# Shield.net
KiCad netlist of a schematic drawn in EAGLE
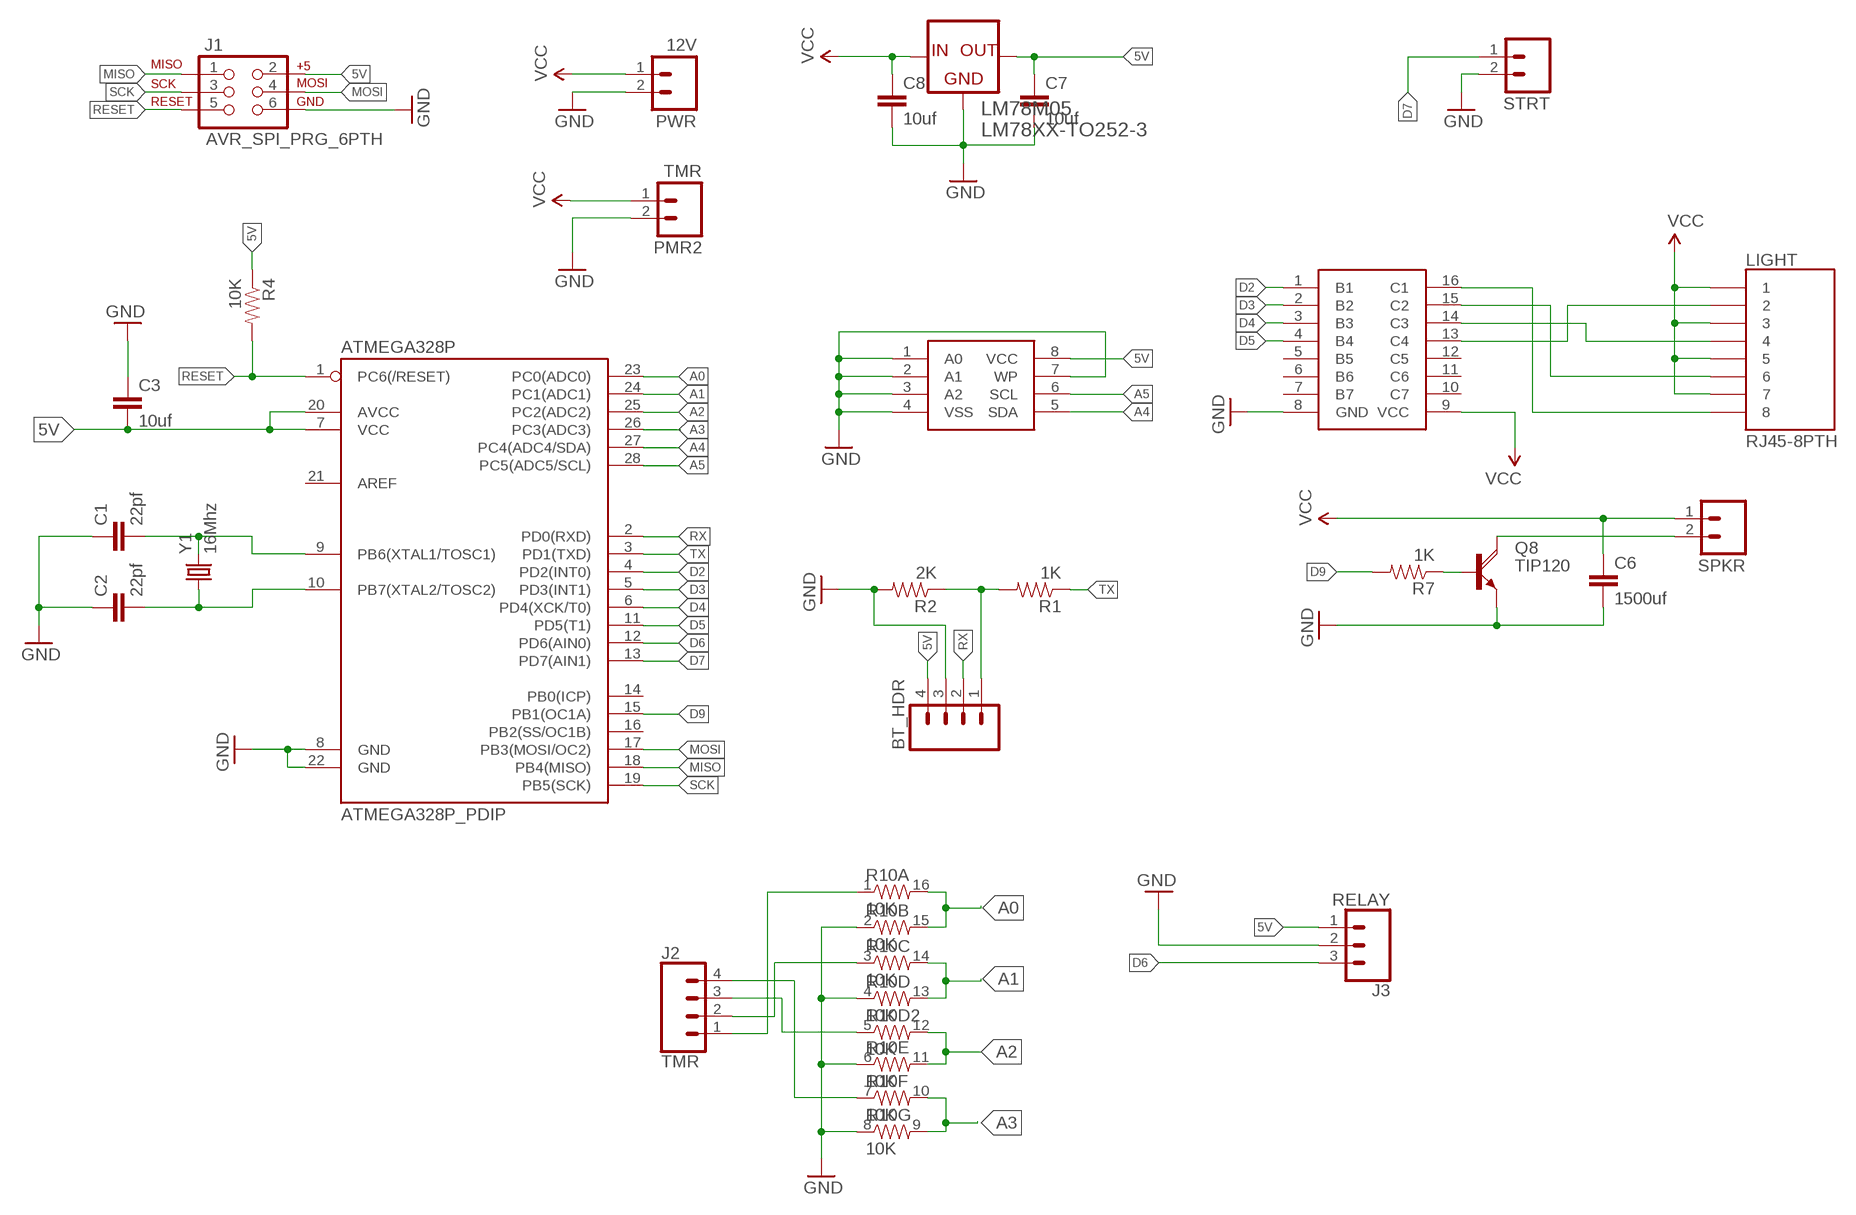
[diagram p0: schematic, sheet 1]

(export (version "E")
  (design (tool "Eeschema 10.0.6"))
  (components
    (comp (ref "24AA512")
      (value "24AAXXX")
      (footprint "eagle-import:SOIC-8-EIAJ")
      (libsource (lib "eagle-import") (part "24AAXXX"))
    )
    (comp (ref "ATMEGA328P")
      (value "ATMEGA328P_PDIP")
      (footprint "eagle-import:DIL28-3")
      (libsource (lib "eagle-import") (part "ATMEGA328P_PDIP"))
    )
    (comp (ref "BT_HDR")
      (value "M04PTH")
      (footprint "eagle-import:1X04@1")
      (libsource (lib "eagle-import") (part "M04PTH"))
    )
    (comp (ref "C1")
      (value "22pf")
      (footprint "eagle-import:1206")
      (libsource (lib "eagle-import") (part "CAP1206"))
    )
    (comp (ref "C2")
      (value "22pf")
      (footprint "eagle-import:1206")
      (libsource (lib "eagle-import") (part "CAP1206"))
    )
    (comp (ref "C3")
      (value "10uf")
      (footprint "eagle-import:1206")
      (libsource (lib "eagle-import") (part "CAP1206"))
    )
    (comp (ref "C6")
      (value "1500uf")
      (footprint "eagle-import:CAP-PTH-5MM")
      (libsource (lib "eagle-import") (part "CAPPTH1"))
    )
    (comp (ref "C7")
      (value "10uf")
      (footprint "eagle-import:CAP-PTH-SMALL")
      (libsource (lib "eagle-import") (part "CAPPTH"))
    )
    (comp (ref "C8")
      (value "10uf")
      (footprint "eagle-import:CAP-PTH-SMALL")
      (libsource (lib "eagle-import") (part "CAPPTH"))
    )
    (comp (ref "J1")
      (value "AVR_SPI_PRG_6PTH")
      (footprint "eagle-import:2X3")
      (libsource (lib "eagle-import") (part "AVR_SPI_PRG_6PTH"))
    )
    (comp (ref "J2")
      (value "TMR")
      (footprint "eagle-import:SCREWTERMINAL-3.5MM-4")
      (libsource (lib "eagle-import") (part "CONN_04SCREW"))
    )
    (comp (ref "J3")
      (value "RELAY")
      (footprint "eagle-import:SCREWTERMINAL-3.5MM-3")
      (libsource (lib "eagle-import") (part "CONN_03SCREW"))
    )
    (comp (ref "LIGHT")
      (value "RJ45-8PTH")
      (footprint "eagle-import:RJ45-8")
      (libsource (lib "eagle-import") (part "RJ45-8PTH"))
    )
    (comp (ref "LM78M05")
      (value "LM78XX-TO252-3")
      (footprint "eagle-import:TO252-3")
      (fields (field (name "MPN") "UA78M33CKVURG3"))
      (libsource (lib "eagle-import") (part "LM78XX-TO252-3"))
    )
    (comp (ref "MC1413D")
      (value "MC1413D")
      (footprint "eagle-import:SO016")
      (libsource (lib "eagle-import") (part "MC1413D"))
    )
    (comp (ref "PMR2")
      (value "TMR")
      (footprint "eagle-import:SCREWTERMINAL-3.5MM-2")
      (libsource (lib "eagle-import") (part "M023.5MM"))
    )
    (comp (ref "PWR")
      (value "12V")
      (footprint "eagle-import:SCREWTERMINAL-3.5MM-2")
      (libsource (lib "eagle-import") (part "M023.5MM"))
    )
    (comp (ref "Q8")
      (value "TIP120")
      (footprint "eagle-import:TO220V")
      (libsource (lib "eagle-import") (part "TIP120"))
    )
    (comp (ref "R1")
      (value "1K")
      (footprint "eagle-import:1206")
      (libsource (lib "eagle-import") (part "RESISTOR1206"))
    )
    (comp (ref "R2")
      (value "2K")
      (footprint "eagle-import:1206")
      (libsource (lib "eagle-import") (part "RESISTOR1206"))
    )
    (comp (ref "R4")
      (value "10K")
      (footprint "eagle-import:1206")
      (libsource (lib "eagle-import") (part "RESISTOR1206"))
    )
    (comp (ref "R7")
      (value "1K")
      (footprint "eagle-import:1206")
      (libsource (lib "eagle-import") (part "RESISTOR1206"))
    )
    (comp (ref "R10")
      (value "10K")
      (footprint "eagle-import:SO016")
      (libsource (lib "eagle-import") (part "RESISTOR-ARRAY"))
    )
    (comp (ref "SPKR")
      (value "M023.5MM")
      (footprint "eagle-import:SCREWTERMINAL-3.5MM-2")
      (libsource (lib "eagle-import") (part "M023.5MM"))
    )
    (comp (ref "STRT")
      (value "M023.5MM")
      (footprint "eagle-import:SCREWTERMINAL-3.5MM-2")
      (libsource (lib "eagle-import") (part "M023.5MM"))
    )
    (comp (ref "Y1")
      (value "16Mhz")
      (footprint "eagle-import:HC49US")
      (libsource (lib "eagle-import") (part "CRYSTALHC49US"))
    )
  )
  (nets
    (net (code "1") (name "5V") (class "Default")
      (node (ref "24AA512") (pin "8") (pinfunction "VCC_8") (pintype "bidirectional"))
      (node (ref "ATMEGA328P") (pin "20") (pinfunction "AVCC_20") (pintype "bidirectional"))
      (node (ref "ATMEGA328P") (pin "7") (pinfunction "VCC_7") (pintype "bidirectional"))
      (node (ref "BT_HDR") (pin "4") (pinfunction "4_4") (pintype "passive"))
      (node (ref "C3") (pin "2") (pinfunction "2_2") (pintype "passive"))
      (node (ref "C7") (pin "1") (pinfunction "1_1") (pintype "passive"))
      (node (ref "J1") (pin "2") (pinfunction "2_2") (pintype "passive"))
      (node (ref "J3") (pin "1") (pinfunction "1_1") (pintype "passive"))
      (node (ref "LM78M05") (pin "3") (pinfunction "OUT_3") (pintype "output"))
      (node (ref "R4") (pin "1") (pinfunction "1_1") (pintype "passive"))
    )
    (net (code "2") (name "A0") (class "Default")
      (node (ref "ATMEGA328P") (pin "23") (pinfunction "PC0(ADC0)_23") (pintype "bidirectional"))
      (node (ref "R10") (pin "15") (pinfunction "2_15") (pintype "passive"))
      (node (ref "R10") (pin "16") (pinfunction "2_16") (pintype "passive"))
    )
    (net (code "3") (name "A1") (class "Default")
      (node (ref "ATMEGA328P") (pin "24") (pinfunction "PC1(ADC1)_24") (pintype "bidirectional"))
      (node (ref "R10") (pin "13") (pinfunction "2_13") (pintype "passive"))
      (node (ref "R10") (pin "14") (pinfunction "2_14") (pintype "passive"))
    )
    (net (code "4") (name "A2") (class "Default")
      (node (ref "ATMEGA328P") (pin "25") (pinfunction "PC2(ADC2)_25") (pintype "bidirectional"))
      (node (ref "R10") (pin "11") (pinfunction "2_11") (pintype "passive"))
      (node (ref "R10") (pin "12") (pinfunction "2_12") (pintype "passive"))
    )
    (net (code "5") (name "A3") (class "Default")
      (node (ref "ATMEGA328P") (pin "26") (pinfunction "PC3(ADC3)_26") (pintype "bidirectional"))
      (node (ref "R10") (pin "10") (pinfunction "2_10") (pintype "passive"))
      (node (ref "R10") (pin "9") (pinfunction "2_9") (pintype "passive"))
    )
    (net (code "6") (name "A4") (class "Default")
      (node (ref "24AA512") (pin "5") (pinfunction "SDA_5") (pintype "bidirectional"))
      (node (ref "ATMEGA328P") (pin "27") (pinfunction "PC4(ADC4/SDA)_27") (pintype "bidirectional"))
    )
    (net (code "7") (name "A5") (class "Default")
      (node (ref "24AA512") (pin "6") (pinfunction "SCL_6") (pintype "bidirectional"))
      (node (ref "ATMEGA328P") (pin "28") (pinfunction "PC5(ADC5/SCL)_28") (pintype "bidirectional"))
    )
    (net (code "8") (name "D2") (class "Default")
      (node (ref "ATMEGA328P") (pin "4") (pinfunction "PD2(INT0)_4") (pintype "bidirectional"))
      (node (ref "MC1413D") (pin "1") (pinfunction "B1_1") (pintype "bidirectional"))
    )
    (net (code "9") (name "D3") (class "Default")
      (node (ref "ATMEGA328P") (pin "5") (pinfunction "PD3(INT1)_5") (pintype "bidirectional"))
      (node (ref "MC1413D") (pin "2") (pinfunction "B2_2") (pintype "bidirectional"))
    )
    (net (code "10") (name "D4") (class "Default")
      (node (ref "ATMEGA328P") (pin "6") (pinfunction "PD4(XCK/T0)_6") (pintype "bidirectional"))
      (node (ref "MC1413D") (pin "3") (pinfunction "B3_3") (pintype "bidirectional"))
    )
    (net (code "11") (name "D5") (class "Default")
      (node (ref "ATMEGA328P") (pin "11") (pinfunction "PD5(T1)_11") (pintype "bidirectional"))
      (node (ref "MC1413D") (pin "4") (pinfunction "B4_4") (pintype "bidirectional"))
    )
    (net (code "12") (name "D6") (class "Default")
      (node (ref "ATMEGA328P") (pin "12") (pinfunction "PD6(AIN0)_12") (pintype "bidirectional"))
      (node (ref "J3") (pin "3") (pinfunction "3_3") (pintype "passive"))
    )
    (net (code "13") (name "D7") (class "Default")
      (node (ref "ATMEGA328P") (pin "13") (pinfunction "PD7(AIN1)_13") (pintype "bidirectional"))
      (node (ref "STRT") (pin "1") (pinfunction "1_1") (pintype "passive"))
    )
    (net (code "14") (name "D9") (class "Default")
      (node (ref "ATMEGA328P") (pin "15") (pinfunction "PB1(OC1A)_15") (pintype "bidirectional"))
      (node (ref "R7") (pin "2") (pinfunction "2_2") (pintype "passive"))
    )
    (net (code "15") (name "GND") (class "Default")
      (node (ref "24AA512") (pin "1") (pinfunction "A0_1") (pintype "bidirectional"))
      (node (ref "24AA512") (pin "2") (pinfunction "A1_2") (pintype "bidirectional"))
      (node (ref "24AA512") (pin "3") (pinfunction "A2_3") (pintype "bidirectional"))
      (node (ref "24AA512") (pin "4") (pinfunction "VSS_4") (pintype "bidirectional"))
      (node (ref "24AA512") (pin "7") (pinfunction "WP_7") (pintype "bidirectional"))
      (node (ref "ATMEGA328P") (pin "22") (pinfunction "GND_22") (pintype "bidirectional"))
      (node (ref "ATMEGA328P") (pin "8") (pinfunction "GND_8") (pintype "bidirectional"))
      (node (ref "BT_HDR") (pin "3") (pinfunction "3_3") (pintype "passive"))
      (node (ref "C1") (pin "1") (pinfunction "1_1") (pintype "passive"))
      (node (ref "C2") (pin "1") (pinfunction "1_1") (pintype "passive"))
      (node (ref "C3") (pin "1") (pinfunction "1_1") (pintype "passive"))
      (node (ref "C6") (pin "2") (pinfunction "2_2") (pintype "passive"))
      (node (ref "C7") (pin "2") (pinfunction "2_2") (pintype "passive"))
      (node (ref "C8") (pin "2") (pinfunction "2_2") (pintype "passive"))
      (node (ref "J1") (pin "6") (pinfunction "6_6") (pintype "passive"))
      (node (ref "J3") (pin "2") (pinfunction "2_2") (pintype "passive"))
      (node (ref "LM78M05") (pin "2") (pinfunction "COM_2") (pintype "passive"))
      (node (ref "MC1413D") (pin "8") (pinfunction "GND_8") (pintype "bidirectional"))
      (node (ref "PMR2") (pin "2") (pinfunction "2_2") (pintype "passive"))
      (node (ref "PWR") (pin "2") (pinfunction "2_2") (pintype "passive"))
      (node (ref "Q8") (pin "3") (pinfunction "E_3") (pintype "passive"))
      (node (ref "R10") (pin "2") (pinfunction "1_2") (pintype "passive"))
      (node (ref "R10") (pin "4") (pinfunction "1_4") (pintype "passive"))
      (node (ref "R10") (pin "6") (pinfunction "1_6") (pintype "passive"))
      (node (ref "R10") (pin "8") (pinfunction "1_8") (pintype "passive"))
      (node (ref "R2") (pin "2") (pinfunction "2_2") (pintype "passive"))
      (node (ref "STRT") (pin "2") (pinfunction "2_2") (pintype "passive"))
    )
    (net (code "16") (name "MISO") (class "Default")
      (node (ref "ATMEGA328P") (pin "18") (pinfunction "PB4(MISO)_18") (pintype "bidirectional"))
      (node (ref "J1") (pin "1") (pinfunction "1_1") (pintype "passive"))
    )
    (net (code "17") (name "MOSI") (class "Default")
      (node (ref "ATMEGA328P") (pin "17") (pinfunction "PB3(MOSI/OC2)_17") (pintype "bidirectional"))
      (node (ref "J1") (pin "4") (pinfunction "4_4") (pintype "passive"))
    )
    (net (code "18") (name "Net-(ATMEGA328P-PB6(XTAL1{slash}TOSC1))") (class "Default")
      (node (ref "ATMEGA328P") (pin "9") (pinfunction "PB6(XTAL1/TOSC1)_9") (pintype "bidirectional"))
      (node (ref "C1") (pin "2") (pinfunction "2_2") (pintype "passive"))
      (node (ref "Y1") (pin "2") (pinfunction "2_2") (pintype "passive"))
    )
    (net (code "19") (name "Net-(ATMEGA328P-PB7(XTAL2{slash}TOSC2))") (class "Default")
      (node (ref "ATMEGA328P") (pin "10") (pinfunction "PB7(XTAL2/TOSC2)_10") (pintype "bidirectional"))
      (node (ref "C2") (pin "2") (pinfunction "2_2") (pintype "passive"))
      (node (ref "Y1") (pin "1") (pinfunction "1_1") (pintype "passive"))
    )
    (net (code "20") (name "Net-(BT_HDR-Pad1)") (class "Default")
      (node (ref "BT_HDR") (pin "1") (pinfunction "1_1") (pintype "passive"))
      (node (ref "R1") (pin "2") (pinfunction "2_2") (pintype "passive"))
      (node (ref "R2") (pin "1") (pinfunction "1_1") (pintype "passive"))
    )
    (net (code "21") (name "Net-(J2-Pad1)") (class "Default")
      (node (ref "J2") (pin "1") (pinfunction "1_1") (pintype "passive"))
      (node (ref "R10") (pin "1") (pinfunction "1_1") (pintype "passive"))
    )
    (net (code "22") (name "Net-(MC1413D-C1)") (class "Default")
      (node (ref "LIGHT") (pin "8") (pinfunction "8_8") (pintype "bidirectional"))
      (node (ref "MC1413D") (pin "16") (pinfunction "C1_16") (pintype "bidirectional"))
    )
    (net (code "23") (name "Net-(MC1413D-C2)") (class "Default")
      (node (ref "LIGHT") (pin "6") (pinfunction "6_6") (pintype "bidirectional"))
      (node (ref "MC1413D") (pin "15") (pinfunction "C2_15") (pintype "bidirectional"))
    )
    (net (code "24") (name "Net-(MC1413D-C3)") (class "Default")
      (node (ref "LIGHT") (pin "4") (pinfunction "4_4") (pintype "bidirectional"))
      (node (ref "MC1413D") (pin "14") (pinfunction "C3_14") (pintype "bidirectional"))
    )
    (net (code "25") (name "Net-(MC1413D-C4)") (class "Default")
      (node (ref "LIGHT") (pin "2") (pinfunction "2_2") (pintype "bidirectional"))
      (node (ref "MC1413D") (pin "13") (pinfunction "C4_13") (pintype "bidirectional"))
    )
    (net (code "26") (name "Net-(Q8-B)") (class "Default")
      (node (ref "Q8") (pin "1") (pinfunction "B_1") (pintype "passive"))
      (node (ref "R7") (pin "1") (pinfunction "1_1") (pintype "passive"))
    )
    (net (code "27") (name "Net-(Q8-C)") (class "Default")
      (node (ref "Q8") (pin "2") (pinfunction "C_2") (pintype "passive"))
      (node (ref "SPKR") (pin "2") (pinfunction "2_2") (pintype "passive"))
    )
    (net (code "28") (name "Net-(R10C-1)") (class "Default")
      (node (ref "J2") (pin "2") (pinfunction "2_2") (pintype "passive"))
      (node (ref "R10") (pin "3") (pinfunction "1_3") (pintype "passive"))
    )
    (net (code "29") (name "Net-(R10E-1)") (class "Default")
      (node (ref "J2") (pin "3") (pinfunction "3_3") (pintype "passive"))
      (node (ref "R10") (pin "5") (pinfunction "1_5") (pintype "passive"))
    )
    (net (code "30") (name "Net-(R10G-1)") (class "Default")
      (node (ref "J2") (pin "4") (pinfunction "4_4") (pintype "passive"))
      (node (ref "R10") (pin "7") (pinfunction "1_7") (pintype "passive"))
    )
    (net (code "31") (name "RESET") (class "Default")
      (node (ref "ATMEGA328P") (pin "1") (pinfunction "PC6(/RESET)_1") (pintype "bidirectional"))
      (node (ref "J1") (pin "5") (pinfunction "5_5") (pintype "passive"))
      (node (ref "R4") (pin "2") (pinfunction "2_2") (pintype "passive"))
    )
    (net (code "32") (name "RX") (class "Default")
      (node (ref "ATMEGA328P") (pin "2") (pinfunction "PD0(RXD)_2") (pintype "bidirectional"))
      (node (ref "BT_HDR") (pin "2") (pinfunction "2_2") (pintype "passive"))
    )
    (net (code "33") (name "SCK") (class "Default")
      (node (ref "ATMEGA328P") (pin "19") (pinfunction "PB5(SCK)_19") (pintype "bidirectional"))
      (node (ref "J1") (pin "3") (pinfunction "3_3") (pintype "passive"))
    )
    (net (code "34") (name "TX") (class "Default")
      (node (ref "ATMEGA328P") (pin "3") (pinfunction "PD1(TXD)_3") (pintype "bidirectional"))
      (node (ref "R1") (pin "1") (pinfunction "1_1") (pintype "passive"))
    )
    (net (code "35") (name "VCC") (class "Default")
      (node (ref "C6") (pin "1") (pinfunction "1_1") (pintype "passive"))
      (node (ref "C8") (pin "1") (pinfunction "1_1") (pintype "passive"))
      (node (ref "LIGHT") (pin "1") (pinfunction "1_1") (pintype "bidirectional"))
      (node (ref "LIGHT") (pin "3") (pinfunction "3_3") (pintype "bidirectional"))
      (node (ref "LIGHT") (pin "5") (pinfunction "5_5") (pintype "bidirectional"))
      (node (ref "LIGHT") (pin "7") (pinfunction "7_7") (pintype "bidirectional"))
      (node (ref "LM78M05") (pin "1") (pinfunction "IN_1") (pintype "input"))
      (node (ref "MC1413D") (pin "9") (pinfunction "VCC_9") (pintype "bidirectional"))
      (node (ref "PMR2") (pin "1") (pinfunction "1_1") (pintype "passive"))
      (node (ref "PWR") (pin "1") (pinfunction "1_1") (pintype "passive"))
      (node (ref "SPKR") (pin "1") (pinfunction "1_1") (pintype "passive"))
    )
    (net (code "36") (name "unconnected-(ATMEGA328P-AREF-Pad21)") (class "Default")
      (node (ref "ATMEGA328P") (pin "21") (pinfunction "AREF_21") (pintype "bidirectional"))
    )
    (net (code "37") (name "unconnected-(ATMEGA328P-PB0(ICP)-Pad14)") (class "Default")
      (node (ref "ATMEGA328P") (pin "14") (pinfunction "PB0(ICP)_14") (pintype "bidirectional"))
    )
    (net (code "38") (name "unconnected-(ATMEGA328P-PB2(SS{slash}OC1B)-Pad16)") (class "Default")
      (node (ref "ATMEGA328P") (pin "16") (pinfunction "PB2(SS/OC1B)_16") (pintype "bidirectional"))
    )
    (net (code "39") (name "unconnected-(MC1413D-B5-Pad5)") (class "Default")
      (node (ref "MC1413D") (pin "5") (pinfunction "B5_5") (pintype "bidirectional"))
    )
    (net (code "40") (name "unconnected-(MC1413D-B6-Pad6)") (class "Default")
      (node (ref "MC1413D") (pin "6") (pinfunction "B6_6") (pintype "bidirectional"))
    )
    (net (code "41") (name "unconnected-(MC1413D-B7-Pad7)") (class "Default")
      (node (ref "MC1413D") (pin "7") (pinfunction "B7_7") (pintype "bidirectional"))
    )
    (net (code "42") (name "unconnected-(MC1413D-C5-Pad12)") (class "Default")
      (node (ref "MC1413D") (pin "12") (pinfunction "C5_12") (pintype "bidirectional"))
    )
    (net (code "43") (name "unconnected-(MC1413D-C6-Pad11)") (class "Default")
      (node (ref "MC1413D") (pin "11") (pinfunction "C6_11") (pintype "bidirectional"))
    )
    (net (code "44") (name "unconnected-(MC1413D-C7-Pad10)") (class "Default")
      (node (ref "MC1413D") (pin "10") (pinfunction "C7_10") (pintype "bidirectional"))
    )
  )
)
